# STM32F030F4_RF433_TRIAC_LEARN_CODE.net
KiCad netlist of a schematic drawn in Altium Designer
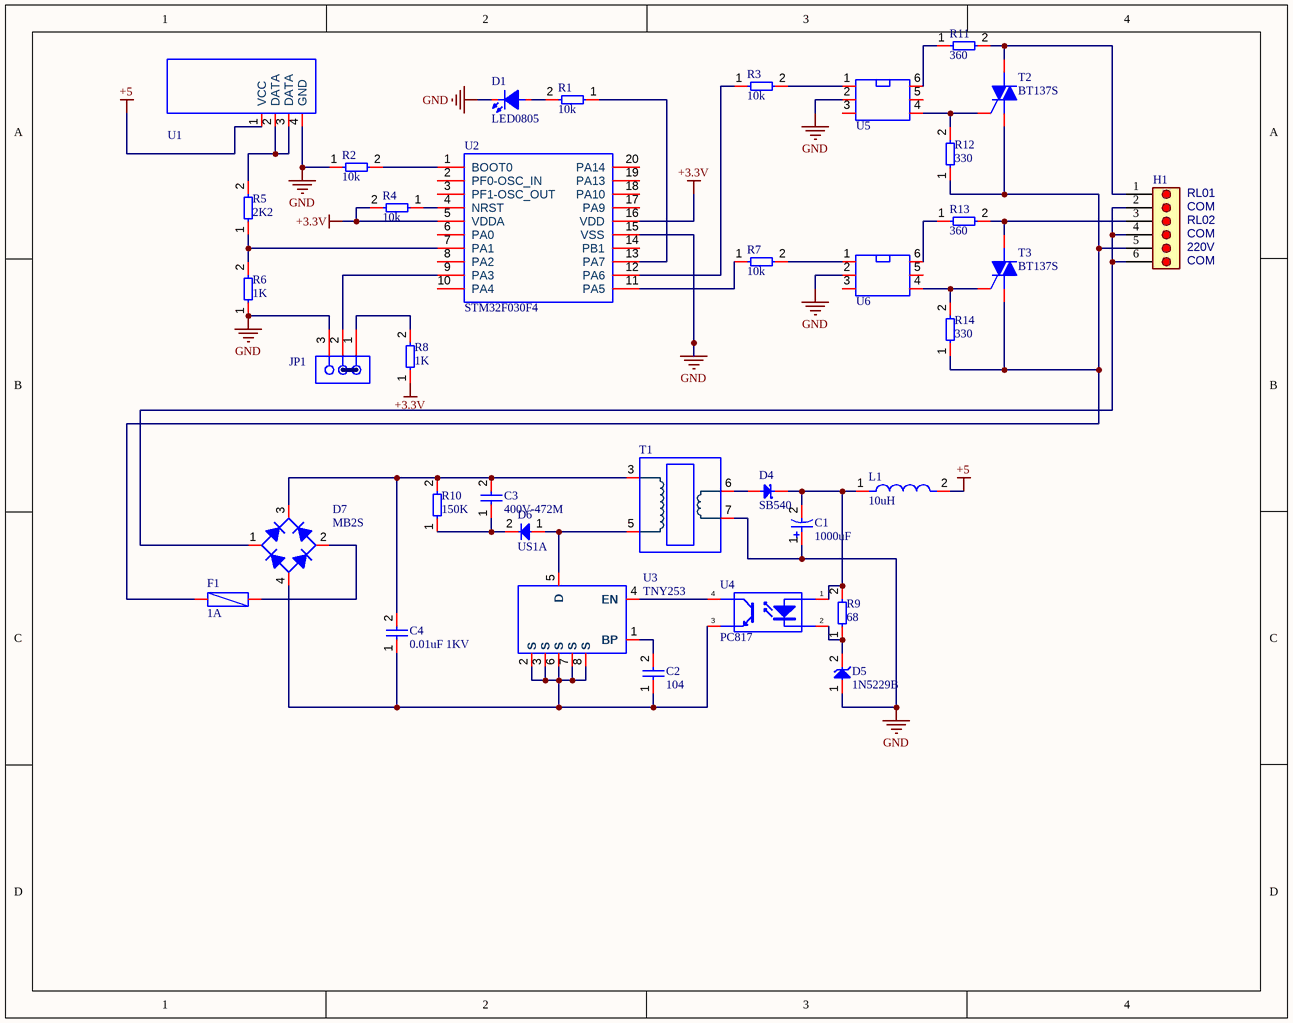
[diagram p0: STM32F030F4_RF433_TRIAC_LEARN_CODE.SchDoc]

(export (version "E")
  (design (tool "Eeschema 10.0.6"))
  (components
    (comp (ref "C1")
      (value "1000uF")
      (footprint "CAP_RAD_4mm")
      (libsource (lib "Lib31082020") (part "Capacitor(Radian)"))
    )
    (comp (ref "C2") (value "104") (footprint "C0805") (libsource (lib "Lib31082020") (part "C0805")))
    (comp (ref "C3") (value "400V-472M") (footprint "C0805") (libsource (lib "Lib31082020") (part "C0805")))
    (comp (ref "C4")
      (value "0.01uF 1KV")
      (footprint "C1812")
      (libsource (lib "Lib31082020") (part "Capacitors(SMD)"))
    )
    (comp (ref "D1")
      (value "LED0805")
      (footprint "L0805RED")
      (libsource (lib "Lib31082020") (part "LED0805"))
    )
    (comp (ref "D4")
      (value "SB540")
      (footprint "DO-214AC(SMA)")
      (libsource (lib "Lib31082020") (part "Diode Schottky"))
    )
    (comp (ref "D5")
      (value "1N5229B")
      (footprint "DO-213AB")
      (libsource (lib "Lib31082020") (part "Diode Zener"))
    )
    (comp (ref "D6")
      (value "US1A")
      (footprint "DO-214AC(SMA)")
      (libsource (lib "Lib31082020") (part "US1A-US1M"))
    )
    (comp (ref "D7")
      (value "MB2S")
      (footprint "TO-269AA")
      (libsource (lib "Lib31082020") (part "Diode MB2S"))
    )
    (comp (ref "F1") (value "1A") (footprint "FUSE1812") (libsource (lib "Lib31082020") (part "Fuse")))
    (comp (ref "H1")
      (value "Header Big 6")
      (footprint "HEADER BIG 6")
      (libsource (lib "Library 3D") (part "Header Big 6"))
    )
    (comp (ref "JP1")
      (value "Header 3x1 TH Pitch 2.54mm")
      (footprint "Header 3x1 TH Pitch 2.54mm")
      (libsource (lib "Lib31082020") (part "Header 3x1 TH Pitch 2.54mm"))
    )
    (comp (ref "L1")
      (value "10uH")
      (footprint "INDUCTOR_1206")
      (libsource (lib "Lib31082020") (part "Inductor"))
    )
    (comp (ref "R1") (value "10k") (footprint "R0805") (libsource (lib "") (part "Resistor SMD_2")))
    (comp (ref "R2") (value "10k") (footprint "R0805") (libsource (lib "") (part "Resistor SMD_1")))
    (comp (ref "R3") (value "10k") (footprint "R0805") (libsource (lib "") (part "Resistor SMD_1")))
    (comp (ref "R4") (value "10k") (footprint "R0805") (libsource (lib "") (part "Resistor SMD_2")))
    (comp (ref "R5") (value "2K2") (footprint "R0805") (libsource (lib "Lib31082020") (part "Resistor SMD")))
    (comp (ref "R6") (value "1K") (footprint "R0805") (libsource (lib "Lib31082020") (part "Resistor SMD")))
    (comp (ref "R7") (value "10k") (footprint "R0805") (libsource (lib "") (part "Resistor SMD_1")))
    (comp (ref "R8") (value "1K") (footprint "R0805") (libsource (lib "Lib31082020") (part "Resistor SMD")))
    (comp (ref "R9") (value "68") (footprint "R0805") (libsource (lib "Lib31082020") (part "Resistor SMD")))
    (comp (ref "R10")
      (value "150K")
      (footprint "R0805")
      (libsource (lib "Lib31082020") (part "Resistor SMD"))
    )
    (comp (ref "R11") (value "360") (footprint "R0805") (libsource (lib "") (part "Resistor SMD_1")))
    (comp (ref "R12") (value "330") (footprint "R0805") (libsource (lib "Lib31082020") (part "Resistor SMD")))
    (comp (ref "R13") (value "360") (footprint "R0805") (libsource (lib "") (part "Resistor SMD_1")))
    (comp (ref "R14") (value "330") (footprint "R0805") (libsource (lib "Lib31082020") (part "Resistor SMD")))
    (comp (ref "T1")
      (value "TRANSFORMER_EE16A")
      (footprint "TRANSFORMER_EE16A")
      (libsource (lib "Lib31082020") (part "TRANSFORMER_EE16A"))
    )
    (comp (ref "T2")
      (value "BT137S")
      (footprint "TO252-3")
      (libsource (lib "Lib31082020") (part "BT137S-600E(8A 600V)"))
    )
    (comp (ref "T3")
      (value "BT137S")
      (footprint "TO252-3")
      (libsource (lib "Lib31082020") (part "BT137S-600E(8A 600V)"))
    )
    (comp (ref "U1")
      (value "RF433_315_RECEVICE")
      (footprint "RF433_315_RECEVICE")
      (libsource (lib "Lib31082020") (part "RF433_315"))
    )
    (comp (ref "U2")
      (value "STM32F030F4")
      (footprint "TSSOP20_0.65_4.4")
      (description "4Kbyte RAM and 16Kb FLASH")
      (libsource (lib "Lib31082020") (part "STM32F030F4"))
    )
    (comp (ref "U3")
      (value "TNY253")
      (footprint "SOIC08_1.27_6.0")
      (libsource (lib "Lib31082020") (part "TNY253"))
    )
    (comp (ref "U4") (value "PC817") (footprint "DIP4") (libsource (lib "Lib31082020") (part "PC817")))
    (comp (ref "U5") (value "NC") (footprint "DIP6_White") (libsource (lib "Lib31082020") (part "MOC3041")))
    (comp (ref "U6") (value "NC") (footprint "DIP6_White") (libsource (lib "Lib31082020") (part "MOC3041")))
  )
  (nets
    (net (code "1") (name "+3.3V") (class "Default")
      (node (ref "R4") (pin "2") (pinfunction "2_2") (pintype "passive"))
      (node (ref "R8") (pin "1") (pinfunction "1_1") (pintype "passive"))
      (node (ref "U2") (pin "16") (pinfunction "VDD_16") (pintype "passive"))
      (node (ref "U2") (pin "5") (pinfunction "VDDA_5") (pintype "passive"))
    )
    (net (code "2") (name "+5") (class "Default")
      (node (ref "L1") (pin "2") (pinfunction "2_2") (pintype "passive"))
      (node (ref "U1") (pin "1") (pinfunction "VCC_1") (pintype "passive"))
    )
    (net (code "3") (name "GND") (class "Default")
      (node (ref "C1") (pin "1") (pinfunction "1_1") (pintype "passive"))
      (node (ref "D1") (pin "2") (pinfunction "K_2") (pintype "passive"))
      (node (ref "D5") (pin "1") (pinfunction "1_1") (pintype "passive"))
      (node (ref "JP1") (pin "3") (pinfunction "3_3") (pintype "passive"))
      (node (ref "R2") (pin "1") (pinfunction "1_1") (pintype "passive"))
      (node (ref "R6") (pin "1") (pinfunction "1_1") (pintype "passive"))
      (node (ref "T1") (pin "7") (pinfunction "6_7") (pintype "passive"))
      (node (ref "U1") (pin "4") (pinfunction "GND_4") (pintype "passive"))
      (node (ref "U2") (pin "15") (pinfunction "VSS_15") (pintype "passive"))
      (node (ref "U5") (pin "2") (pinfunction "K_2") (pintype "passive"))
      (node (ref "U6") (pin "2") (pinfunction "K_2") (pintype "passive"))
    )
    (net (code "4") (name "Net-(C3-Pad1)") (class "Default")
      (node (ref "C3") (pin "1") (pinfunction "1_1") (pintype "passive"))
      (node (ref "D6") (pin "2") (pinfunction "2_2") (pintype "passive"))
      (node (ref "R10") (pin "1") (pinfunction "1_1") (pintype "passive"))
    )
    (net (code "5") (name "Net-(C3-Pad2)") (class "Default")
      (node (ref "C3") (pin "2") (pinfunction "2_2") (pintype "passive"))
      (node (ref "C4") (pin "2") (pinfunction "2_2") (pintype "passive"))
      (node (ref "D7") (pin "3") (pinfunction "3_3") (pintype "passive"))
      (node (ref "R10") (pin "2") (pinfunction "2_2") (pintype "passive"))
      (node (ref "T1") (pin "3") (pinfunction "3_3") (pintype "passive"))
    )
    (net (code "6") (name "Net-(D1-A)") (class "Default")
      (node (ref "D1") (pin "1") (pinfunction "A_1") (pintype "passive"))
      (node (ref "R1") (pin "2") (pinfunction "2_2") (pintype "passive"))
    )
    (net (code "7") (name "Net-(D4-A)") (class "Default")
      (node (ref "D4") (pin "1") (pinfunction "A_1") (pintype "passive"))
      (node (ref "T1") (pin "6") (pinfunction "6_6") (pintype "passive"))
    )
    (net (code "8") (name "Net-(D4-K)") (class "Default")
      (node (ref "C1") (pin "2") (pinfunction "2_2") (pintype "passive"))
      (node (ref "D4") (pin "2") (pinfunction "K_2") (pintype "passive"))
      (node (ref "L1") (pin "1") (pinfunction "1_1") (pintype "passive"))
      (node (ref "R9") (pin "2") (pinfunction "2_2") (pintype "passive"))
      (node (ref "U4") (pin "1") (pinfunction "A_1") (pintype "passive"))
    )
    (net (code "9") (name "Net-(D7-Pad1)") (class "Default")
      (node (ref "D7") (pin "1") (pinfunction "1_1") (pintype "passive"))
      (node (ref "H1") (pin "2") (pinfunction "2_2") (pintype "passive"))
      (node (ref "H1") (pin "4") (pinfunction "4_4") (pintype "passive"))
      (node (ref "H1") (pin "6") (pinfunction "6_6") (pintype "passive"))
    )
    (net (code "10") (name "Net-(D7-Pad2)") (class "Default")
      (node (ref "D7") (pin "2") (pinfunction "2_2") (pintype "passive"))
      (node (ref "F1") (pin "2") (pinfunction "2_2") (pintype "passive"))
    )
    (net (code "11") (name "Net-(JP1-Pad1)") (class "Default")
      (node (ref "JP1") (pin "1") (pinfunction "1_1") (pintype "passive"))
      (node (ref "R8") (pin "2") (pinfunction "2_2") (pintype "passive"))
    )
    (net (code "12") (name "Net-(R5-Pad2)") (class "Default")
      (node (ref "R5") (pin "2") (pinfunction "2_2") (pintype "passive"))
      (node (ref "U1") (pin "2") (pinfunction "DATA_2") (pintype "passive"))
      (node (ref "U1") (pin "3") (pinfunction "DATA_3") (pintype "passive"))
    )
    (net (code "13") (name "Net-(R11-Pad1)") (class "Default")
      (node (ref "R11") (pin "1") (pinfunction "1_1") (pintype "passive"))
      (node (ref "U5") (pin "6") (pinfunction "MAIN_TERMINAL_6") (pintype "passive"))
    )
    (net (code "14") (name "Net-(R13-Pad1)") (class "Default")
      (node (ref "R13") (pin "1") (pinfunction "1_1") (pintype "passive"))
      (node (ref "U6") (pin "6") (pinfunction "MAIN_TERMINAL_6") (pintype "passive"))
    )
    (net (code "15") (name "Net-(T2-G)") (class "Default")
      (node (ref "R12") (pin "2") (pinfunction "2_2") (pintype "passive"))
      (node (ref "T2") (pin "3") (pinfunction "G_3") (pintype "passive"))
      (node (ref "U5") (pin "4") (pinfunction "MAIN_TERMINAL_4") (pintype "passive"))
    )
    (net (code "16") (name "Net-(T2-T1)") (class "Default")
      (node (ref "F1") (pin "1") (pinfunction "1_1") (pintype "passive"))
      (node (ref "H1") (pin "5") (pinfunction "5_5") (pintype "passive"))
      (node (ref "R12") (pin "1") (pinfunction "1_1") (pintype "passive"))
      (node (ref "R14") (pin "1") (pinfunction "1_1") (pintype "passive"))
      (node (ref "T2") (pin "1") (pinfunction "T1_1") (pintype "passive"))
      (node (ref "T3") (pin "1") (pinfunction "T1_1") (pintype "passive"))
    )
    (net (code "17") (name "Net-(T2-T2)") (class "Default")
      (node (ref "H1") (pin "1") (pinfunction "1_1") (pintype "passive"))
      (node (ref "R11") (pin "2") (pinfunction "2_2") (pintype "passive"))
      (node (ref "T2") (pin "2") (pinfunction "T2_2") (pintype "passive"))
    )
    (net (code "18") (name "Net-(T3-G)") (class "Default")
      (node (ref "R14") (pin "2") (pinfunction "2_2") (pintype "passive"))
      (node (ref "T3") (pin "3") (pinfunction "G_3") (pintype "passive"))
      (node (ref "U6") (pin "4") (pinfunction "MAIN_TERMINAL_4") (pintype "passive"))
    )
    (net (code "19") (name "Net-(T3-T2)") (class "Default")
      (node (ref "H1") (pin "3") (pinfunction "3_3") (pintype "passive"))
      (node (ref "R13") (pin "2") (pinfunction "2_2") (pintype "passive"))
      (node (ref "T3") (pin "2") (pinfunction "T2_2") (pintype "passive"))
    )
    (net (code "20") (name "Net-(U2-BOOT0)") (class "Default")
      (node (ref "R2") (pin "2") (pinfunction "2_2") (pintype "passive"))
      (node (ref "U2") (pin "1") (pinfunction "BOOT0_1") (pintype "passive"))
    )
    (net (code "21") (name "Net-(U2-NRST)") (class "Default")
      (node (ref "R4") (pin "1") (pinfunction "1_1") (pintype "passive"))
      (node (ref "U2") (pin "4") (pinfunction "NRST_4") (pintype "passive"))
    )
    (net (code "22") (name "Net-(U2-PA1)") (class "Default")
      (node (ref "R5") (pin "1") (pinfunction "1_1") (pintype "passive"))
      (node (ref "R6") (pin "2") (pinfunction "2_2") (pintype "passive"))
      (node (ref "U2") (pin "7") (pinfunction "PA1_7") (pintype "passive"))
    )
    (net (code "23") (name "Net-(U2-PA3)") (class "Default")
      (node (ref "JP1") (pin "2") (pinfunction "2_2") (pintype "passive"))
      (node (ref "U2") (pin "9") (pinfunction "PA3_9") (pintype "passive"))
    )
    (net (code "24") (name "Net-(U2-PA5)") (class "Default")
      (node (ref "R7") (pin "1") (pinfunction "1_1") (pintype "passive"))
      (node (ref "U2") (pin "11") (pinfunction "PA5_11") (pintype "passive"))
    )
    (net (code "25") (name "Net-(U2-PA6)") (class "Default")
      (node (ref "R3") (pin "1") (pinfunction "1_1") (pintype "passive"))
      (node (ref "U2") (pin "12") (pinfunction "PA6_12") (pintype "passive"))
    )
    (net (code "26") (name "Net-(U2-PA7)") (class "Default")
      (node (ref "R1") (pin "1") (pinfunction "1_1") (pintype "passive"))
      (node (ref "U2") (pin "13") (pinfunction "PA7_13") (pintype "passive"))
    )
    (net (code "27") (name "Net-(U3-BP)") (class "Default")
      (node (ref "C2") (pin "2") (pinfunction "2_2") (pintype "passive"))
      (node (ref "U3") (pin "1") (pinfunction "BP_1") (pintype "passive"))
    )
    (net (code "28") (name "Net-(U3-D)") (class "Default")
      (node (ref "D6") (pin "1") (pinfunction "1_1") (pintype "passive"))
      (node (ref "T1") (pin "5") (pinfunction "5_5") (pintype "passive"))
      (node (ref "U3") (pin "5") (pinfunction "D_5") (pintype "passive"))
    )
    (net (code "29") (name "Net-(U3-EN)") (class "Default")
      (node (ref "U3") (pin "4") (pinfunction "EN_4") (pintype "passive"))
      (node (ref "U4") (pin "4") (pinfunction "C_4") (pintype "passive"))
    )
    (net (code "30") (name "Net-(U4-E)") (class "Default")
      (node (ref "C2") (pin "1") (pinfunction "1_1") (pintype "passive"))
      (node (ref "C4") (pin "1") (pinfunction "1_1") (pintype "passive"))
      (node (ref "D7") (pin "4") (pinfunction "4_4") (pintype "passive"))
      (node (ref "U3") (pin "2") (pinfunction "S_2") (pintype "passive"))
      (node (ref "U3") (pin "3") (pinfunction "S_3") (pintype "passive"))
      (node (ref "U3") (pin "6") (pinfunction "S_6") (pintype "passive"))
      (node (ref "U3") (pin "7") (pinfunction "S_7") (pintype "passive"))
      (node (ref "U3") (pin "8") (pinfunction "S_8") (pintype "passive"))
      (node (ref "U4") (pin "3") (pinfunction "E_3") (pintype "passive"))
    )
    (net (code "31") (name "Net-(U4-K)") (class "Default")
      (node (ref "D5") (pin "2") (pinfunction "2_2") (pintype "passive"))
      (node (ref "R9") (pin "1") (pinfunction "1_1") (pintype "passive"))
      (node (ref "U4") (pin "2") (pinfunction "K_2") (pintype "passive"))
    )
    (net (code "32") (name "Net-(U5-A)") (class "Default")
      (node (ref "R3") (pin "2") (pinfunction "2_2") (pintype "passive"))
      (node (ref "U5") (pin "1") (pinfunction "A_1") (pintype "passive"))
    )
    (net (code "33") (name "Net-(U6-A)") (class "Default")
      (node (ref "R7") (pin "2") (pinfunction "2_2") (pintype "passive"))
      (node (ref "U6") (pin "1") (pinfunction "A_1") (pintype "passive"))
    )
    (net (code "34") (name "unconnected-(U2-PA0-Pad6)") (class "Default")
      (node (ref "U2") (pin "6") (pinfunction "PA0_6") (pintype "passive"))
    )
    (net (code "35") (name "unconnected-(U2-PA2-Pad8)") (class "Default")
      (node (ref "U2") (pin "8") (pinfunction "PA2_8") (pintype "passive"))
    )
    (net (code "36") (name "unconnected-(U2-PA4-Pad10)") (class "Default")
      (node (ref "U2") (pin "10") (pinfunction "PA4_10") (pintype "passive"))
    )
    (net (code "37") (name "unconnected-(U2-PA9-Pad17)") (class "Default")
      (node (ref "U2") (pin "17") (pinfunction "PA9_17") (pintype "passive"))
    )
    (net (code "38") (name "unconnected-(U2-PA10-Pad18)") (class "Default")
      (node (ref "U2") (pin "18") (pinfunction "PA10_18") (pintype "passive"))
    )
    (net (code "39") (name "unconnected-(U2-PA13-Pad19)") (class "Default")
      (node (ref "U2") (pin "19") (pinfunction "PA13_19") (pintype "passive"))
    )
    (net (code "40") (name "unconnected-(U2-PA14-Pad20)") (class "Default")
      (node (ref "U2") (pin "20") (pinfunction "PA14_20") (pintype "passive"))
    )
    (net (code "41") (name "unconnected-(U2-PB1-Pad14)") (class "Default")
      (node (ref "U2") (pin "14") (pinfunction "PB1_14") (pintype "passive"))
    )
    (net (code "42") (name "unconnected-(U2-PF0-OSC_IN-Pad2)") (class "Default")
      (node (ref "U2") (pin "2") (pinfunction "PF0-OSC_IN_2") (pintype "passive"))
    )
    (net (code "43") (name "unconnected-(U2-PF1-OSC_OUT-Pad3)") (class "Default")
      (node (ref "U2") (pin "3") (pinfunction "PF1-OSC_OUT_3") (pintype "passive"))
    )
    (net (code "44") (name "unconnected-(U5-NC-Pad3)") (class "Default")
      (node (ref "U5") (pin "3") (pinfunction "NC_3") (pintype "passive"))
    )
    (net (code "45") (name "unconnected-(U5-Pad5)") (class "Default")
      (node (ref "U5") (pin "5") (pinfunction "5_5") (pintype "passive"))
    )
    (net (code "46") (name "unconnected-(U6-NC-Pad3)") (class "Default")
      (node (ref "U6") (pin "3") (pinfunction "NC_3") (pintype "passive"))
    )
    (net (code "47") (name "unconnected-(U6-Pad5)") (class "Default")
      (node (ref "U6") (pin "5") (pinfunction "5_5") (pintype "passive"))
    )
  )
)
